# 05.net
KiCad netlist of a schematic drawn in Altium Designer
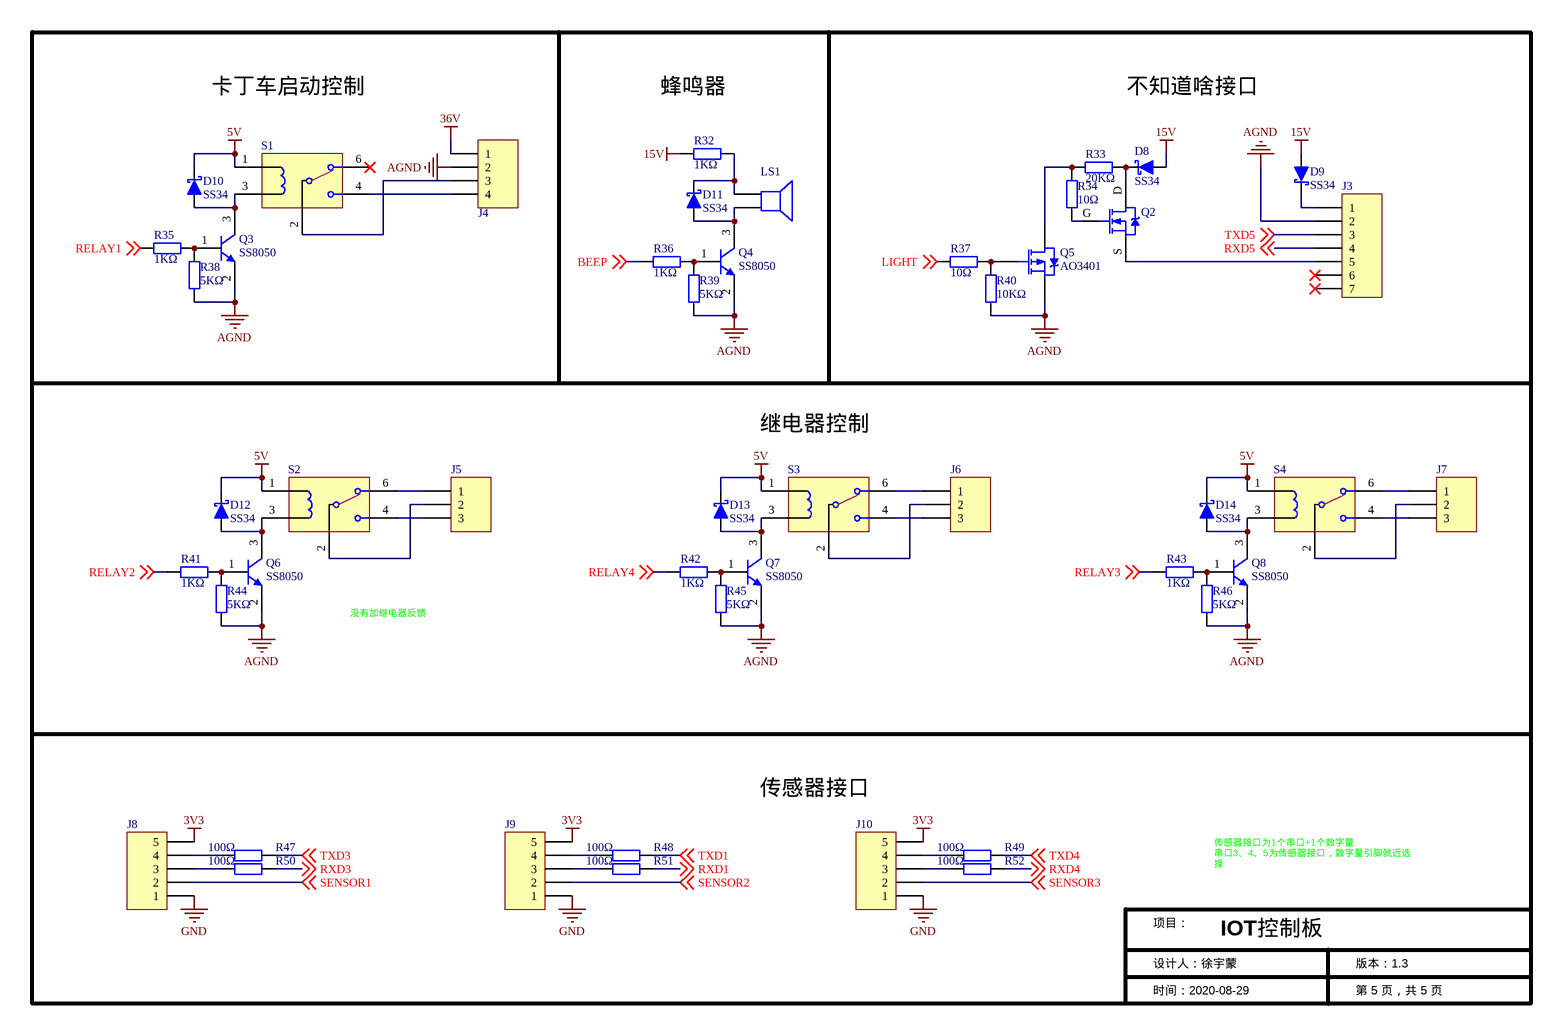
[diagram p0: 05_外部接口与其他部分.SchDoc]

(export (version "E")
  (design (tool "Eeschema 10.0.6"))
  (components
    (comp (ref "D8")
      (value "SS34")
      (footprint "SMA(DO-214AC)")
      (description "Schottky Diode")
      (fields (field (name "PUBLISHER") "Altium Limited"))
      (libsource (lib "元件库") (part "D Schottky"))
    )
    (comp (ref "D9")
      (value "SS34")
      (footprint "SMA(DO-214AC)")
      (description "Schottky Diode")
      (fields (field (name "PUBLISHER") "Altium Limited"))
      (libsource (lib "元件库") (part "D Schottky"))
    )
    (comp (ref "D10")
      (value "SS34")
      (footprint "SMA(DO-214AC)")
      (description "Schottky Diode")
      (fields (field (name "PUBLISHER") "Altium Limited"))
      (libsource (lib "元件库") (part "D Schottky"))
    )
    (comp (ref "D11")
      (value "SS34")
      (footprint "SMA(DO-214AC)")
      (description "Schottky Diode")
      (fields (field (name "PUBLISHER") "Altium Limited"))
      (libsource (lib "元件库") (part "D Schottky"))
    )
    (comp (ref "D12")
      (value "SS34")
      (footprint "SMA(DO-214AC)")
      (description "Schottky Diode")
      (fields (field (name "PUBLISHER") "Altium Limited"))
      (libsource (lib "元件库") (part "D Schottky"))
    )
    (comp (ref "D13")
      (value "SS34")
      (footprint "SMA(DO-214AC)")
      (description "Schottky Diode")
      (fields (field (name "PUBLISHER") "Altium Limited"))
      (libsource (lib "元件库") (part "D Schottky"))
    )
    (comp (ref "D14")
      (value "SS34")
      (footprint "SMA(DO-214AC)")
      (description "Schottky Diode")
      (fields (field (name "PUBLISHER") "Altium Limited"))
      (libsource (lib "元件库") (part "D Schottky"))
    )
    (comp (ref "J3")
      (value "Header7")
      (footprint "Header_7X1_XH_2.54_弯针")
      (description "接插件")
      (libsource (lib "Arrowy_Racing") (part "Header7"))
    )
    (comp (ref "J4")
      (value "Header 4")
      (footprint "Header_4P_XH_2.54_弯脚")
      (description "接插件")
      (fields (field (name "PUBLISHER") "Altium Limited"))
      (libsource (lib "Arrowy_Racing") (part "Header 4"))
    )
    (comp (ref "J5")
      (value "Header3")
      (footprint "Header_3X1_XH_2.54_弯脚")
      (description "接插件")
      (libsource (lib "Arrowy_Racing") (part "Header3"))
    )
    (comp (ref "J6")
      (value "Header3")
      (footprint "Header_3X1_XH_2.54_弯脚")
      (description "接插件")
      (libsource (lib "Arrowy_Racing") (part "Header3"))
    )
    (comp (ref "J7")
      (value "Header3")
      (footprint "Header_3X1_XH_2.54_弯脚")
      (description "接插件")
      (libsource (lib "Arrowy_Racing") (part "Header3"))
    )
    (comp (ref "J8")
      (value "Header5")
      (footprint "Header_5X1_XH_2.54_弯针")
      (description "接插件")
      (libsource (lib "Arrowy_Racing") (part "Header5"))
    )
    (comp (ref "J9")
      (value "Header5")
      (footprint "Header_5X1_XH_2.54_弯针")
      (description "接插件")
      (libsource (lib "Arrowy_Racing") (part "Header5"))
    )
    (comp (ref "J10")
      (value "Header5")
      (footprint "Header_5X1_XH_2.54_弯针")
      (description "接插件")
      (libsource (lib "Arrowy_Racing") (part "Header5"))
    )
    (comp (ref "LS1")
      (value "蜂鸣器")
      (footprint "蜂鸣器 9*5mm")
      (description "Loudspeaker")
      (fields (field (name "PUBLISHER") "Altium Limited"))
      (libsource (lib "Arrowy_Racing") (part "Speaker"))
    )
    (comp (ref "Q2")
      (value "AO3400")
      (footprint "SOT-23-MOSFET")
      (description "N沟道MOS管")
      (libsource (lib "Arrowy_Racing") (part "MOSFET-N"))
    )
    (comp (ref "Q3")
      (value "SS8050")
      (footprint "SOT-23")
      (description "NPN贴片三极管")
      (fields (field (name "PUBLISHER") "Altium Limited"))
      (libsource (lib "Arrowy_Racing") (part "SS8050"))
    )
    (comp (ref "Q4")
      (value "SS8050")
      (footprint "SOT-23")
      (description "NPN贴片三极管")
      (fields (field (name "PUBLISHER") "Altium Limited"))
      (libsource (lib "Arrowy_Racing") (part "SS8050"))
    )
    (comp (ref "Q5")
      (value "AO3401")
      (footprint "SOT-23-MOSFET")
      (description "P沟道MOS管")
      (libsource (lib "Arrowy_Racing") (part "MOSFET-P"))
    )
    (comp (ref "Q6")
      (value "SS8050")
      (footprint "SOT-23")
      (description "NPN贴片三极管")
      (fields (field (name "PUBLISHER") "Altium Limited"))
      (libsource (lib "Arrowy_Racing") (part "SS8050"))
    )
    (comp (ref "Q7")
      (value "SS8050")
      (footprint "SOT-23")
      (description "NPN贴片三极管")
      (fields (field (name "PUBLISHER") "Altium Limited"))
      (libsource (lib "Arrowy_Racing") (part "SS8050"))
    )
    (comp (ref "Q8")
      (value "SS8050")
      (footprint "SOT-23")
      (description "NPN贴片三极管")
      (fields (field (name "PUBLISHER") "Altium Limited"))
      (libsource (lib "Arrowy_Racing") (part "SS8050"))
    )
    (comp (ref "R32")
      (value "1KΩ")
      (footprint "0603")
      (description "贴片电阻")
      (fields (field (name "Comment") "Res") (field (name "PUBLISHER") "Altium Limited"))
      (libsource (lib "Arrowy_Racing") (part "Res"))
    )
    (comp (ref "R33")
      (value "20KΩ")
      (footprint "0603")
      (description "贴片电阻")
      (fields (field (name "Comment") "Res") (field (name "PUBLISHER") "Altium Limited"))
      (libsource (lib "Arrowy_Racing") (part "Res"))
    )
    (comp (ref "R34")
      (value "10Ω")
      (footprint "0603")
      (description "贴片电阻")
      (fields (field (name "Comment") "Res") (field (name "PUBLISHER") "Altium Limited"))
      (libsource (lib "") (part "Res_2"))
    )
    (comp (ref "R35")
      (value "1KΩ")
      (footprint "0603")
      (description "贴片电阻")
      (fields (field (name "Comment") "Res") (field (name "PUBLISHER") "Altium Limited"))
      (libsource (lib "Arrowy_Racing") (part "Res"))
    )
    (comp (ref "R36")
      (value "1KΩ")
      (footprint "0603")
      (description "贴片电阻")
      (fields (field (name "Comment") "Res") (field (name "PUBLISHER") "Altium Limited"))
      (libsource (lib "Arrowy_Racing") (part "Res"))
    )
    (comp (ref "R37")
      (value "10Ω")
      (footprint "0603")
      (description "贴片电阻")
      (fields (field (name "Comment") "Res") (field (name "PUBLISHER") "Altium Limited"))
      (libsource (lib "Arrowy_Racing") (part "Res"))
    )
    (comp (ref "R38")
      (value "5KΩ")
      (footprint "0603")
      (description "贴片电阻")
      (fields (field (name "Comment") "Res") (field (name "PUBLISHER") "Altium Limited"))
      (libsource (lib "") (part "Res_3"))
    )
    (comp (ref "R39")
      (value "5KΩ")
      (footprint "0603")
      (description "贴片电阻")
      (fields (field (name "Comment") "Res") (field (name "PUBLISHER") "Altium Limited"))
      (libsource (lib "") (part "Res_3"))
    )
    (comp (ref "R40")
      (value "10KΩ")
      (footprint "0603")
      (description "贴片电阻")
      (fields (field (name "Comment") "Res") (field (name "PUBLISHER") "Altium Limited"))
      (libsource (lib "") (part "Res_3"))
    )
    (comp (ref "R41")
      (value "1KΩ")
      (footprint "0603")
      (description "贴片电阻")
      (fields (field (name "Comment") "Res") (field (name "PUBLISHER") "Altium Limited"))
      (libsource (lib "Arrowy_Racing") (part "Res"))
    )
    (comp (ref "R42")
      (value "1KΩ")
      (footprint "0603")
      (description "贴片电阻")
      (fields (field (name "Comment") "Res") (field (name "PUBLISHER") "Altium Limited"))
      (libsource (lib "Arrowy_Racing") (part "Res"))
    )
    (comp (ref "R43")
      (value "1KΩ")
      (footprint "0603")
      (description "贴片电阻")
      (fields (field (name "Comment") "Res") (field (name "PUBLISHER") "Altium Limited"))
      (libsource (lib "Arrowy_Racing") (part "Res"))
    )
    (comp (ref "R44")
      (value "5KΩ")
      (footprint "0603")
      (description "贴片电阻")
      (fields (field (name "Comment") "Res") (field (name "PUBLISHER") "Altium Limited"))
      (libsource (lib "") (part "Res_3"))
    )
    (comp (ref "R45")
      (value "5KΩ")
      (footprint "0603")
      (description "贴片电阻")
      (fields (field (name "Comment") "Res") (field (name "PUBLISHER") "Altium Limited"))
      (libsource (lib "") (part "Res_3"))
    )
    (comp (ref "R46")
      (value "5KΩ")
      (footprint "0603")
      (description "贴片电阻")
      (fields (field (name "Comment") "Res") (field (name "PUBLISHER") "Altium Limited"))
      (libsource (lib "") (part "Res_3"))
    )
    (comp (ref "R47")
      (value "100Ω")
      (footprint "0603")
      (description "贴片电阻")
      (fields (field (name "Comment") "Res") (field (name "PUBLISHER") "Altium Limited"))
      (libsource (lib "") (part "Res_1"))
    )
    (comp (ref "R48")
      (value "100Ω")
      (footprint "0603")
      (description "贴片电阻")
      (fields (field (name "Comment") "Res") (field (name "PUBLISHER") "Altium Limited"))
      (libsource (lib "") (part "Res_1"))
    )
    (comp (ref "R49")
      (value "100Ω")
      (footprint "0603")
      (description "贴片电阻")
      (fields (field (name "Comment") "Res") (field (name "PUBLISHER") "Altium Limited"))
      (libsource (lib "") (part "Res_1"))
    )
    (comp (ref "R50")
      (value "100Ω")
      (footprint "0603")
      (description "贴片电阻")
      (fields (field (name "Comment") "Res") (field (name "PUBLISHER") "Altium Limited"))
      (libsource (lib "") (part "Res_1"))
    )
    (comp (ref "R51")
      (value "100Ω")
      (footprint "0603")
      (description "贴片电阻")
      (fields (field (name "Comment") "Res") (field (name "PUBLISHER") "Altium Limited"))
      (libsource (lib "") (part "Res_1"))
    )
    (comp (ref "R52")
      (value "100Ω")
      (footprint "0603")
      (description "贴片电阻")
      (fields (field (name "Comment") "Res") (field (name "PUBLISHER") "Altium Limited"))
      (libsource (lib "") (part "Res_1"))
    )
    (comp (ref "S1")
      (value "Delay")
      (footprint "SongLe_Relay")
      (description "松乐继电器")
      (libsource (lib "Arrowy_Racing") (part "SongLe_Relay"))
    )
    (comp (ref "S2")
      (value "Delay")
      (footprint "SongLe_Relay")
      (description "松乐继电器")
      (libsource (lib "Arrowy_Racing") (part "SongLe_Relay"))
    )
    (comp (ref "S3")
      (value "Delay")
      (footprint "SongLe_Relay")
      (description "松乐继电器")
      (libsource (lib "Arrowy_Racing") (part "SongLe_Relay"))
    )
    (comp (ref "S4")
      (value "Delay")
      (footprint "SongLe_Relay")
      (description "松乐继电器")
      (libsource (lib "Arrowy_Racing") (part "SongLe_Relay"))
    )
  )
  (nets
    (net (code "1") (name "3V3") (class "Default")
      (node (ref "J10") (pin "5") (pinfunction "5_5") (pintype "passive"))
      (node (ref "J8") (pin "5") (pinfunction "5_5") (pintype "passive"))
      (node (ref "J9") (pin "5") (pinfunction "5_5") (pintype "passive"))
    )
    (net (code "2") (name "5V") (class "Default")
      (node (ref "D10") (pin "2") (pinfunction "K_2") (pintype "passive"))
      (node (ref "D12") (pin "2") (pinfunction "K_2") (pintype "passive"))
      (node (ref "D13") (pin "2") (pinfunction "K_2") (pintype "passive"))
      (node (ref "D14") (pin "2") (pinfunction "K_2") (pintype "passive"))
      (node (ref "S1") (pin "1") (pinfunction "1_1") (pintype "passive"))
      (node (ref "S2") (pin "1") (pinfunction "1_1") (pintype "passive"))
      (node (ref "S3") (pin "1") (pinfunction "1_1") (pintype "passive"))
      (node (ref "S4") (pin "1") (pinfunction "1_1") (pintype "passive"))
    )
    (net (code "3") (name "15V") (class "Default")
      (node (ref "D8") (pin "1") (pinfunction "A_1") (pintype "passive"))
      (node (ref "D9") (pin "1") (pinfunction "A_1") (pintype "passive"))
      (node (ref "R32") (pin "2") (pinfunction "2_2") (pintype "passive"))
    )
    (net (code "4") (name "36V") (class "Default")
      (node (ref "J4") (pin "1") (pinfunction "1_1") (pintype "passive"))
    )
    (net (code "5") (name "AGND") (class "Default")
      (node (ref "J3") (pin "2") (pinfunction "2_2") (pintype "passive"))
      (node (ref "J4") (pin "2") (pinfunction "2_2") (pintype "passive"))
      (node (ref "Q3") (pin "2") (pinfunction "E_2") (pintype "passive"))
      (node (ref "Q4") (pin "2") (pinfunction "E_2") (pintype "passive"))
      (node (ref "Q5") (pin "S") (pinfunction "S_S") (pintype "passive"))
      (node (ref "Q6") (pin "2") (pinfunction "E_2") (pintype "passive"))
      (node (ref "Q7") (pin "2") (pinfunction "E_2") (pintype "passive"))
      (node (ref "Q8") (pin "2") (pinfunction "E_2") (pintype "passive"))
      (node (ref "R38") (pin "1") (pinfunction "1_1") (pintype "passive"))
      (node (ref "R39") (pin "1") (pinfunction "1_1") (pintype "passive"))
      (node (ref "R40") (pin "1") (pinfunction "1_1") (pintype "passive"))
      (node (ref "R44") (pin "1") (pinfunction "1_1") (pintype "passive"))
      (node (ref "R45") (pin "1") (pinfunction "1_1") (pintype "passive"))
      (node (ref "R46") (pin "1") (pinfunction "1_1") (pintype "passive"))
    )
    (net (code "6") (name "BEEP") (class "Default")
      (node (ref "R36") (pin "2") (pinfunction "2_2") (pintype "passive"))
    )
    (net (code "7") (name "GND") (class "Default")
      (node (ref "J10") (pin "1") (pinfunction "1_1") (pintype "passive"))
      (node (ref "J8") (pin "1") (pinfunction "1_1") (pintype "passive"))
      (node (ref "J9") (pin "1") (pinfunction "1_1") (pintype "passive"))
    )
    (net (code "8") (name "LIGHT") (class "Default")
      (node (ref "R37") (pin "2") (pinfunction "2_2") (pintype "passive"))
    )
    (net (code "9") (name "Net-(D8-K)") (class "Default")
      (node (ref "D8") (pin "2") (pinfunction "K_2") (pintype "passive"))
      (node (ref "Q2") (pin "D") (pinfunction "D_D") (pintype "passive"))
      (node (ref "R33") (pin "1") (pinfunction "1_1") (pintype "passive"))
    )
    (net (code "10") (name "Net-(D9-K)") (class "Default")
      (node (ref "D9") (pin "2") (pinfunction "K_2") (pintype "passive"))
      (node (ref "J3") (pin "1") (pinfunction "1_1") (pintype "passive"))
    )
    (net (code "11") (name "Net-(D10-A)") (class "Default")
      (node (ref "D10") (pin "1") (pinfunction "A_1") (pintype "passive"))
      (node (ref "Q3") (pin "3") (pinfunction "C_3") (pintype "passive"))
      (node (ref "S1") (pin "3") (pinfunction "3_3") (pintype "passive"))
    )
    (net (code "12") (name "Net-(D11-A)") (class "Default")
      (node (ref "D11") (pin "1") (pinfunction "A_1") (pintype "passive"))
      (node (ref "LS1") (pin "2") (pinfunction "2_2") (pintype "passive"))
      (node (ref "Q4") (pin "3") (pinfunction "C_3") (pintype "passive"))
    )
    (net (code "13") (name "Net-(D11-K)") (class "Default")
      (node (ref "D11") (pin "2") (pinfunction "K_2") (pintype "passive"))
      (node (ref "LS1") (pin "1") (pinfunction "1_1") (pintype "passive"))
      (node (ref "R32") (pin "1") (pinfunction "1_1") (pintype "passive"))
    )
    (net (code "14") (name "Net-(D12-A)") (class "Default")
      (node (ref "D12") (pin "1") (pinfunction "A_1") (pintype "passive"))
      (node (ref "Q6") (pin "3") (pinfunction "C_3") (pintype "passive"))
      (node (ref "S2") (pin "3") (pinfunction "3_3") (pintype "passive"))
    )
    (net (code "15") (name "Net-(D13-A)") (class "Default")
      (node (ref "D13") (pin "1") (pinfunction "A_1") (pintype "passive"))
      (node (ref "Q7") (pin "3") (pinfunction "C_3") (pintype "passive"))
      (node (ref "S3") (pin "3") (pinfunction "3_3") (pintype "passive"))
    )
    (net (code "16") (name "Net-(D14-A)") (class "Default")
      (node (ref "D14") (pin "1") (pinfunction "A_1") (pintype "passive"))
      (node (ref "Q8") (pin "3") (pinfunction "C_3") (pintype "passive"))
      (node (ref "S4") (pin "3") (pinfunction "3_3") (pintype "passive"))
    )
    (net (code "17") (name "Net-(J3-Pad5)") (class "Default")
      (node (ref "J3") (pin "5") (pinfunction "5_5") (pintype "passive"))
      (node (ref "Q2") (pin "S") (pinfunction "S_S") (pintype "passive"))
    )
    (net (code "18") (name "Net-(J4-Pad3)") (class "Default")
      (node (ref "J4") (pin "3") (pinfunction "3_3") (pintype "passive"))
      (node (ref "S1") (pin "2") (pinfunction "2_2") (pintype "passive"))
    )
    (net (code "19") (name "Net-(J4-Pad4)") (class "Default")
      (node (ref "J4") (pin "4") (pinfunction "4_4") (pintype "passive"))
      (node (ref "S1") (pin "4") (pinfunction "4_4") (pintype "passive"))
    )
    (net (code "20") (name "Net-(J5-Pad1)") (class "Default")
      (node (ref "J5") (pin "1") (pinfunction "1_1") (pintype "passive"))
      (node (ref "S2") (pin "6") (pinfunction "6_6") (pintype "passive"))
    )
    (net (code "21") (name "Net-(J5-Pad2)") (class "Default")
      (node (ref "J5") (pin "2") (pinfunction "2_2") (pintype "passive"))
      (node (ref "S2") (pin "2") (pinfunction "2_2") (pintype "passive"))
    )
    (net (code "22") (name "Net-(J5-Pad3)") (class "Default")
      (node (ref "J5") (pin "3") (pinfunction "3_3") (pintype "passive"))
      (node (ref "S2") (pin "4") (pinfunction "4_4") (pintype "passive"))
    )
    (net (code "23") (name "Net-(J6-Pad1)") (class "Default")
      (node (ref "J6") (pin "1") (pinfunction "1_1") (pintype "passive"))
      (node (ref "S3") (pin "6") (pinfunction "6_6") (pintype "passive"))
    )
    (net (code "24") (name "Net-(J6-Pad2)") (class "Default")
      (node (ref "J6") (pin "2") (pinfunction "2_2") (pintype "passive"))
      (node (ref "S3") (pin "2") (pinfunction "2_2") (pintype "passive"))
    )
    (net (code "25") (name "Net-(J6-Pad3)") (class "Default")
      (node (ref "J6") (pin "3") (pinfunction "3_3") (pintype "passive"))
      (node (ref "S3") (pin "4") (pinfunction "4_4") (pintype "passive"))
    )
    (net (code "26") (name "Net-(J7-Pad1)") (class "Default")
      (node (ref "J7") (pin "1") (pinfunction "1_1") (pintype "passive"))
      (node (ref "S4") (pin "6") (pinfunction "6_6") (pintype "passive"))
    )
    (net (code "27") (name "Net-(J7-Pad2)") (class "Default")
      (node (ref "J7") (pin "2") (pinfunction "2_2") (pintype "passive"))
      (node (ref "S4") (pin "2") (pinfunction "2_2") (pintype "passive"))
    )
    (net (code "28") (name "Net-(J7-Pad3)") (class "Default")
      (node (ref "J7") (pin "3") (pinfunction "3_3") (pintype "passive"))
      (node (ref "S4") (pin "4") (pinfunction "4_4") (pintype "passive"))
    )
    (net (code "29") (name "Net-(J8-Pad3)") (class "Default")
      (node (ref "J8") (pin "3") (pinfunction "3_3") (pintype "passive"))
      (node (ref "R50") (pin "1") (pinfunction "1_1") (pintype "passive"))
    )
    (net (code "30") (name "Net-(J8-Pad4)") (class "Default")
      (node (ref "J8") (pin "4") (pinfunction "4_4") (pintype "passive"))
      (node (ref "R47") (pin "1") (pinfunction "1_1") (pintype "passive"))
    )
    (net (code "31") (name "Net-(J9-Pad3)") (class "Default")
      (node (ref "J9") (pin "3") (pinfunction "3_3") (pintype "passive"))
      (node (ref "R51") (pin "1") (pinfunction "1_1") (pintype "passive"))
    )
    (net (code "32") (name "Net-(J9-Pad4)") (class "Default")
      (node (ref "J9") (pin "4") (pinfunction "4_4") (pintype "passive"))
      (node (ref "R48") (pin "1") (pinfunction "1_1") (pintype "passive"))
    )
    (net (code "33") (name "Net-(J10-Pad3)") (class "Default")
      (node (ref "J10") (pin "3") (pinfunction "3_3") (pintype "passive"))
      (node (ref "R52") (pin "1") (pinfunction "1_1") (pintype "passive"))
    )
    (net (code "34") (name "Net-(J10-Pad4)") (class "Default")
      (node (ref "J10") (pin "4") (pinfunction "4_4") (pintype "passive"))
      (node (ref "R49") (pin "1") (pinfunction "1_1") (pintype "passive"))
    )
    (net (code "35") (name "Net-(Q2-PadG)") (class "Default")
      (node (ref "Q2") (pin "G") (pinfunction "G_G") (pintype "passive"))
      (node (ref "R34") (pin "2") (pinfunction "2_2") (pintype "passive"))
    )
    (net (code "36") (name "Net-(Q3-B)") (class "Default")
      (node (ref "Q3") (pin "1") (pinfunction "B_1") (pintype "passive"))
      (node (ref "R35") (pin "1") (pinfunction "1_1") (pintype "passive"))
      (node (ref "R38") (pin "2") (pinfunction "2_2") (pintype "passive"))
    )
    (net (code "37") (name "Net-(Q4-B)") (class "Default")
      (node (ref "Q4") (pin "1") (pinfunction "B_1") (pintype "passive"))
      (node (ref "R36") (pin "1") (pinfunction "1_1") (pintype "passive"))
      (node (ref "R39") (pin "2") (pinfunction "2_2") (pintype "passive"))
    )
    (net (code "38") (name "Net-(Q5-PadD)") (class "Default")
      (node (ref "Q5") (pin "D") (pinfunction "D_D") (pintype "passive"))
      (node (ref "R33") (pin "2") (pinfunction "2_2") (pintype "passive"))
      (node (ref "R34") (pin "1") (pinfunction "1_1") (pintype "passive"))
    )
    (net (code "39") (name "Net-(Q5-PadG)") (class "Default")
      (node (ref "Q5") (pin "G") (pinfunction "G_G") (pintype "passive"))
      (node (ref "R37") (pin "1") (pinfunction "1_1") (pintype "passive"))
      (node (ref "R40") (pin "2") (pinfunction "2_2") (pintype "passive"))
    )
    (net (code "40") (name "Net-(Q6-B)") (class "Default")
      (node (ref "Q6") (pin "1") (pinfunction "B_1") (pintype "passive"))
      (node (ref "R41") (pin "1") (pinfunction "1_1") (pintype "passive"))
      (node (ref "R44") (pin "2") (pinfunction "2_2") (pintype "passive"))
    )
    (net (code "41") (name "Net-(Q7-B)") (class "Default")
      (node (ref "Q7") (pin "1") (pinfunction "B_1") (pintype "passive"))
      (node (ref "R42") (pin "1") (pinfunction "1_1") (pintype "passive"))
      (node (ref "R45") (pin "2") (pinfunction "2_2") (pintype "passive"))
    )
    (net (code "42") (name "Net-(Q8-B)") (class "Default")
      (node (ref "Q8") (pin "1") (pinfunction "B_1") (pintype "passive"))
      (node (ref "R43") (pin "1") (pinfunction "1_1") (pintype "passive"))
      (node (ref "R46") (pin "2") (pinfunction "2_2") (pintype "passive"))
    )
    (net (code "43") (name "RELAY1") (class "Default")
      (node (ref "R35") (pin "2") (pinfunction "2_2") (pintype "passive"))
    )
    (net (code "44") (name "RELAY2") (class "Default")
      (node (ref "R41") (pin "2") (pinfunction "2_2") (pintype "passive"))
    )
    (net (code "45") (name "RELAY3") (class "Default")
      (node (ref "R43") (pin "2") (pinfunction "2_2") (pintype "passive"))
    )
    (net (code "46") (name "RELAY4") (class "Default")
      (node (ref "R42") (pin "2") (pinfunction "2_2") (pintype "passive"))
    )
    (net (code "47") (name "RXD1") (class "Default")
      (node (ref "R51") (pin "2") (pinfunction "2_2") (pintype "passive"))
    )
    (net (code "48") (name "RXD3") (class "Default")
      (node (ref "R50") (pin "2") (pinfunction "2_2") (pintype "passive"))
    )
    (net (code "49") (name "RXD4") (class "Default")
      (node (ref "R52") (pin "2") (pinfunction "2_2") (pintype "passive"))
    )
    (net (code "50") (name "RXD5") (class "Default")
      (node (ref "J3") (pin "4") (pinfunction "4_4") (pintype "passive"))
    )
    (net (code "51") (name "SENSOR1") (class "Default")
      (node (ref "J8") (pin "2") (pinfunction "2_2") (pintype "passive"))
    )
    (net (code "52") (name "SENSOR2") (class "Default")
      (node (ref "J9") (pin "2") (pinfunction "2_2") (pintype "passive"))
    )
    (net (code "53") (name "SENSOR3") (class "Default")
      (node (ref "J10") (pin "2") (pinfunction "2_2") (pintype "passive"))
    )
    (net (code "54") (name "TXD1") (class "Default")
      (node (ref "R48") (pin "2") (pinfunction "2_2") (pintype "passive"))
    )
    (net (code "55") (name "TXD3") (class "Default")
      (node (ref "R47") (pin "2") (pinfunction "2_2") (pintype "passive"))
    )
    (net (code "56") (name "TXD4") (class "Default")
      (node (ref "R49") (pin "2") (pinfunction "2_2") (pintype "passive"))
    )
    (net (code "57") (name "TXD5") (class "Default")
      (node (ref "J3") (pin "3") (pinfunction "3_3") (pintype "passive"))
    )
    (net (code "58") (name "unconnected-(J3-Pad6)") (class "Default")
      (node (ref "J3") (pin "6") (pinfunction "6_6") (pintype "passive+no_connect"))
    )
    (net (code "59") (name "unconnected-(J3-Pad7)") (class "Default")
      (node (ref "J3") (pin "7") (pinfunction "7_7") (pintype "passive+no_connect"))
    )
    (net (code "60") (name "unconnected-(S1-Pad6)") (class "Default")
      (node (ref "S1") (pin "6") (pinfunction "6_6") (pintype "passive+no_connect"))
    )
  )
)
